# Trem-O-Drive.net
KiCad netlist of a schematic drawn in EAGLE
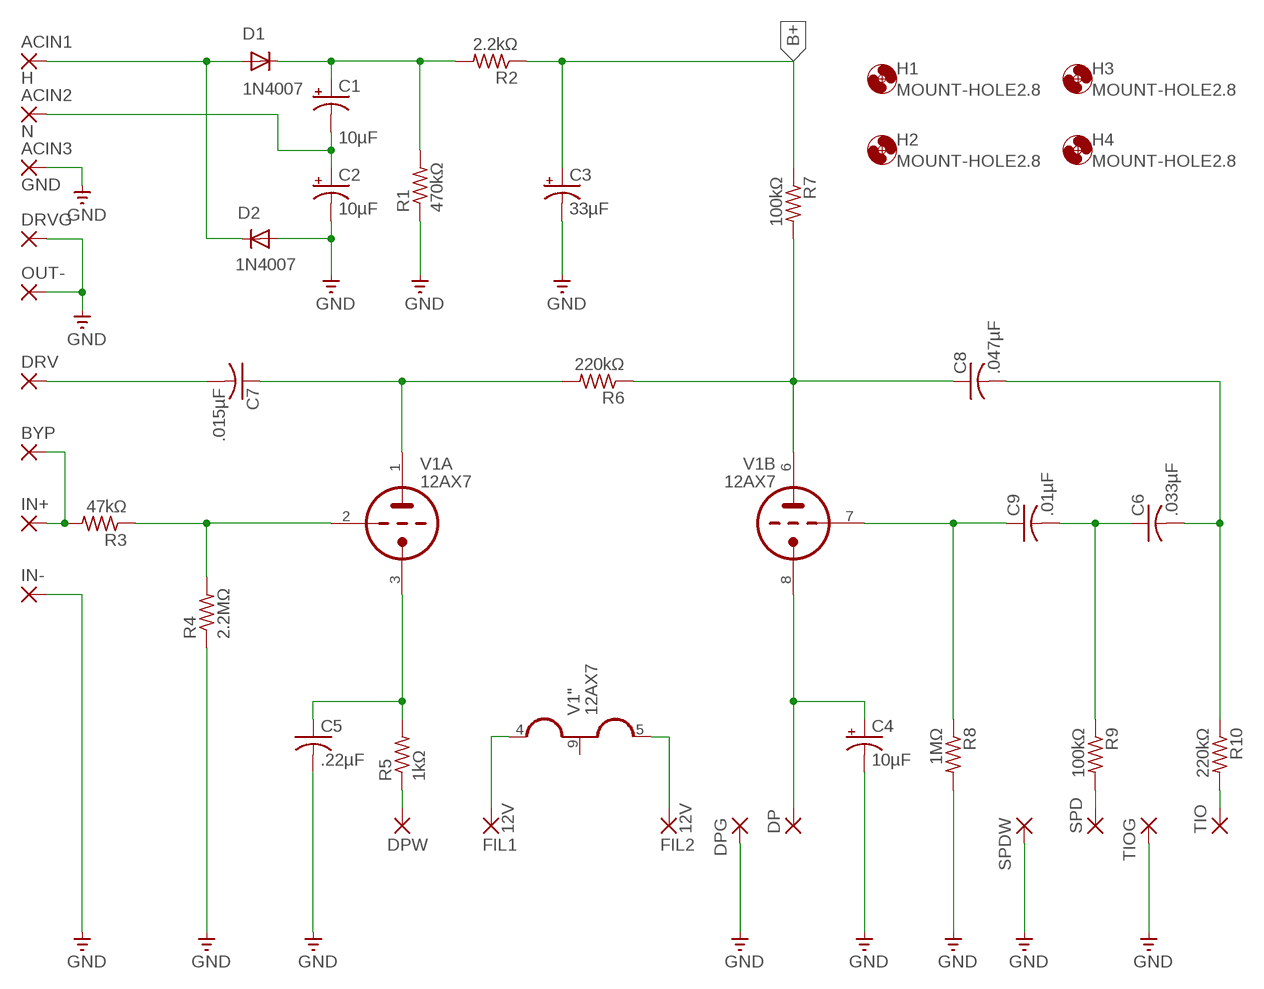
[diagram p0: schematic, sheet 1]

(export (version "E")
  (design (tool "Eeschema 10.0.6"))
  (components
    (comp (ref "ACIN1")
      (value "H")
      (footprint "eagle-import:3,81_1,4")
      (libsource (lib "eagle-import") (part "3,81/1,4"))
    )
    (comp (ref "ACIN2")
      (value "N")
      (footprint "eagle-import:3,81_1,4")
      (libsource (lib "eagle-import") (part "3,81/1,4"))
    )
    (comp (ref "ACIN3")
      (value "GND")
      (footprint "eagle-import:3,81_1,4")
      (libsource (lib "eagle-import") (part "3,81/1,4"))
    )
    (comp (ref "BYP")
      (value "3,81/1,4")
      (footprint "eagle-import:3,81_1,4")
      (libsource (lib "eagle-import") (part "3,81/1,4"))
    )
    (comp (ref "C1")
      (value "10µF")
      (footprint "eagle-import:E5-10,5")
      (libsource (lib "eagle-import") (part "CPOL-USE5-10.5"))
    )
    (comp (ref "C2")
      (value "10µF")
      (footprint "eagle-import:E5-10,5")
      (libsource (lib "eagle-import") (part "CPOL-USE5-10.5"))
    )
    (comp (ref "C3")
      (value "33µF")
      (footprint "eagle-import:E5-10,5")
      (libsource (lib "eagle-import") (part "CPOL-USE5-10.5"))
    )
    (comp (ref "C4")
      (value "10µF")
      (footprint "eagle-import:E5-10,5")
      (libsource (lib "eagle-import") (part "CPOL-USE5-10.5"))
    )
    (comp (ref "C5")
      (value ".22µF")
      (footprint "eagle-import:C150-064X183")
      (libsource (lib "eagle-import") (part "C-US150-064X183"))
    )
    (comp (ref "C6")
      (value ".033µF")
      (footprint "eagle-import:C102-064X133")
      (libsource (lib "eagle-import") (part "C-US102-064X133"))
    )
    (comp (ref "C7")
      (value ".015µF")
      (footprint "eagle-import:C102-064X133")
      (libsource (lib "eagle-import") (part "C-US102-064X133"))
    )
    (comp (ref "C8")
      (value ".047µF")
      (footprint "eagle-import:C102-064X133")
      (libsource (lib "eagle-import") (part "C-US102-064X133"))
    )
    (comp (ref "C9")
      (value ".01µF")
      (footprint "eagle-import:C102-064X133")
      (libsource (lib "eagle-import") (part "C-US102-064X133"))
    )
    (comp (ref "D1")
      (value "1N4007")
      (footprint "eagle-import:DIODE-1N4148")
      (libsource (lib "eagle-import") (part "DIODE1N4148"))
    )
    (comp (ref "D2")
      (value "1N4007")
      (footprint "eagle-import:DIODE-1N4148")
      (libsource (lib "eagle-import") (part "DIODE1N4148"))
    )
    (comp (ref "DP")
      (value "3,81/1,4")
      (footprint "eagle-import:3,81_1,4")
      (libsource (lib "eagle-import") (part "3,81/1,4"))
    )
    (comp (ref "DPG")
      (value "3,81/1,4")
      (footprint "eagle-import:3,81_1,4")
      (libsource (lib "eagle-import") (part "3,81/1,4"))
    )
    (comp (ref "DPW")
      (value "3,81/1,4")
      (footprint "eagle-import:3,81_1,4")
      (libsource (lib "eagle-import") (part "3,81/1,4"))
    )
    (comp (ref "DRV")
      (value "3,81/1,4")
      (footprint "eagle-import:3,81_1,4")
      (libsource (lib "eagle-import") (part "3,81/1,4"))
    )
    (comp (ref "DRVG")
      (value "3,81/1,4")
      (footprint "eagle-import:3,81_1,4")
      (libsource (lib "eagle-import") (part "3,81/1,4"))
    )
    (comp (ref "FIL1")
      (value "12V")
      (footprint "eagle-import:3,81_1,4")
      (libsource (lib "eagle-import") (part "3,81/1,4"))
    )
    (comp (ref "FIL2")
      (value "12V")
      (footprint "eagle-import:3,81_1,4")
      (libsource (lib "eagle-import") (part "3,81/1,4"))
    )
    (comp (ref "H1")
      (value "MOUNT-HOLE2.8")
      (footprint "eagle-import:2,8")
      (libsource (lib "eagle-import") (part "MOUNT-HOLE2.8"))
    )
    (comp (ref "H2")
      (value "MOUNT-HOLE2.8")
      (footprint "eagle-import:2,8")
      (libsource (lib "eagle-import") (part "MOUNT-HOLE2.8"))
    )
    (comp (ref "H3")
      (value "MOUNT-HOLE2.8")
      (footprint "eagle-import:2,8")
      (libsource (lib "eagle-import") (part "MOUNT-HOLE2.8"))
    )
    (comp (ref "H4")
      (value "MOUNT-HOLE2.8")
      (footprint "eagle-import:2,8")
      (libsource (lib "eagle-import") (part "MOUNT-HOLE2.8"))
    )
    (comp (ref "IN+")
      (value "3,81/1,4")
      (footprint "eagle-import:3,81_1,4")
      (libsource (lib "eagle-import") (part "3,81/1,4"))
    )
    (comp (ref "IN-")
      (value "3,81/1,4")
      (footprint "eagle-import:3,81_1,4")
      (libsource (lib "eagle-import") (part "3,81/1,4"))
    )
    (comp (ref "OUT-")
      (value "3,81/1,4")
      (footprint "eagle-import:3,81_1,4")
      (libsource (lib "eagle-import") (part "3,81/1,4"))
    )
    (comp (ref "R1")
      (value "470kΩ")
      (footprint "eagle-import:0411_12")
      (libsource (lib "eagle-import") (part "R-US_0411/12"))
    )
    (comp (ref "R2")
      (value "2.2kΩ")
      (footprint "eagle-import:0411_12")
      (libsource (lib "eagle-import") (part "R-US_0411/12"))
    )
    (comp (ref "R3")
      (value "47kΩ")
      (footprint "eagle-import:0411_12")
      (libsource (lib "eagle-import") (part "R-US_0411/12"))
    )
    (comp (ref "R4")
      (value "2.2MΩ")
      (footprint "eagle-import:0411_12")
      (libsource (lib "eagle-import") (part "R-US_0411/12"))
    )
    (comp (ref "R5")
      (value "1kΩ")
      (footprint "eagle-import:0411_12")
      (libsource (lib "eagle-import") (part "R-US_0411/12"))
    )
    (comp (ref "R6")
      (value "220kΩ")
      (footprint "eagle-import:0411_12")
      (libsource (lib "eagle-import") (part "R-US_0411/12"))
    )
    (comp (ref "R7")
      (value "100kΩ")
      (footprint "eagle-import:0411_12")
      (libsource (lib "eagle-import") (part "R-US_0411/12"))
    )
    (comp (ref "R8")
      (value "1MΩ")
      (footprint "eagle-import:0411_12")
      (libsource (lib "eagle-import") (part "R-US_0411/12"))
    )
    (comp (ref "R9")
      (value "100kΩ")
      (footprint "eagle-import:0411_12")
      (libsource (lib "eagle-import") (part "R-US_0411/12"))
    )
    (comp (ref "R10")
      (value "220kΩ")
      (footprint "eagle-import:0411_12")
      (libsource (lib "eagle-import") (part "R-US_0411/12"))
    )
    (comp (ref "SPD")
      (value "3,81/1,4")
      (footprint "eagle-import:3,81_1,4")
      (libsource (lib "eagle-import") (part "3,81/1,4"))
    )
    (comp (ref "SPDW")
      (value "3,81/1,4")
      (footprint "eagle-import:3,81_1,4")
      (libsource (lib "eagle-import") (part "3,81/1,4"))
    )
    (comp (ref "TIO")
      (value "3,81/1,4")
      (footprint "eagle-import:3,81_1,4")
      (libsource (lib "eagle-import") (part "3,81/1,4"))
    )
    (comp (ref "TIOG")
      (value "3,81/1,4")
      (footprint "eagle-import:3,81_1,4")
      (libsource (lib "eagle-import") (part "3,81/1,4"))
    )
    (comp (ref "V1")
      (value "12AX7")
      (footprint "eagle-import:NOVAL")
      (libsource (lib "eagle-import") (part "12AX7-P"))
    )
  )
  (nets
    (net (code "1") (name "B+") (class "Default")
      (node (ref "C3") (pin "+") (pinfunction "+_+") (pintype "passive"))
      (node (ref "R2") (pin "1") (pinfunction "1_1") (pintype "passive"))
      (node (ref "R7") (pin "1") (pinfunction "1_1") (pintype "passive"))
    )
    (net (code "2") (name "GND") (class "Default")
      (node (ref "ACIN3") (pin "1") (pinfunction "P_1") (pintype "passive"))
      (node (ref "C2") (pin "-") (pinfunction "-_-") (pintype "passive"))
      (node (ref "C3") (pin "-") (pinfunction "-_-") (pintype "passive"))
      (node (ref "C4") (pin "-") (pinfunction "-_-") (pintype "passive"))
      (node (ref "C5") (pin "2") (pinfunction "2_2") (pintype "passive"))
      (node (ref "D2") (pin "A") (pinfunction "A_A") (pintype "passive"))
      (node (ref "DPG") (pin "1") (pinfunction "P_1") (pintype "passive"))
      (node (ref "DRVG") (pin "1") (pinfunction "P_1") (pintype "passive"))
      (node (ref "IN-") (pin "1") (pinfunction "P_1") (pintype "passive"))
      (node (ref "OUT-") (pin "1") (pinfunction "P_1") (pintype "passive"))
      (node (ref "R1") (pin "1") (pinfunction "1_1") (pintype "passive"))
      (node (ref "R4") (pin "1") (pinfunction "1_1") (pintype "passive"))
      (node (ref "R8") (pin "2") (pinfunction "2_2") (pintype "passive"))
      (node (ref "SPDW") (pin "1") (pinfunction "P_1") (pintype "passive"))
      (node (ref "TIOG") (pin "1") (pinfunction "P_1") (pintype "passive"))
    )
    (net (code "3") (name "Net-(ACIN1-P)") (class "Default")
      (node (ref "ACIN1") (pin "1") (pinfunction "P_1") (pintype "passive"))
      (node (ref "D1") (pin "A") (pinfunction "A_A") (pintype "passive"))
      (node (ref "D2") (pin "C") (pinfunction "C_C") (pintype "passive"))
    )
    (net (code "4") (name "Net-(ACIN2-P)") (class "Default")
      (node (ref "ACIN2") (pin "1") (pinfunction "P_1") (pintype "passive"))
      (node (ref "C1") (pin "-") (pinfunction "-_-") (pintype "passive"))
      (node (ref "C2") (pin "+") (pinfunction "+_+") (pintype "passive"))
    )
    (net (code "5") (name "Net-(BYP-P)") (class "Default")
      (node (ref "BYP") (pin "1") (pinfunction "P_1") (pintype "passive"))
      (node (ref "IN+") (pin "1") (pinfunction "P_1") (pintype "passive"))
      (node (ref "R3") (pin "2") (pinfunction "2_2") (pintype "passive"))
    )
    (net (code "6") (name "Net-(C1-Pad+)") (class "Default")
      (node (ref "C1") (pin "+") (pinfunction "+_+") (pintype "passive"))
      (node (ref "D1") (pin "C") (pinfunction "C_C") (pintype "passive"))
      (node (ref "R1") (pin "2") (pinfunction "2_2") (pintype "passive"))
      (node (ref "R2") (pin "2") (pinfunction "2_2") (pintype "passive"))
    )
    (net (code "7") (name "Net-(C6-Pad1)") (class "Default")
      (node (ref "C6") (pin "1") (pinfunction "1_1") (pintype "passive"))
      (node (ref "C9") (pin "2") (pinfunction "2_2") (pintype "passive"))
      (node (ref "R9") (pin "1") (pinfunction "1_1") (pintype "passive"))
    )
    (net (code "8") (name "Net-(C6-Pad2)") (class "Default")
      (node (ref "C6") (pin "2") (pinfunction "2_2") (pintype "passive"))
      (node (ref "C8") (pin "2") (pinfunction "2_2") (pintype "passive"))
      (node (ref "R10") (pin "1") (pinfunction "1_1") (pintype "passive"))
    )
    (net (code "9") (name "Net-(DP-P)") (class "Default")
      (node (ref "C4") (pin "+") (pinfunction "+_+") (pintype "passive"))
      (node (ref "DP") (pin "1") (pinfunction "P_1") (pintype "passive"))
      (node (ref "V1") (pin "8") (pinfunction "TK_8") (pintype "passive"))
    )
    (net (code "10") (name "Net-(DPW-P)") (class "Default")
      (node (ref "DPW") (pin "1") (pinfunction "P_1") (pintype "passive"))
      (node (ref "R5") (pin "1") (pinfunction "1_1") (pintype "passive"))
    )
    (net (code "11") (name "Net-(DRV-P)") (class "Default")
      (node (ref "C7") (pin "2") (pinfunction "2_2") (pintype "passive"))
      (node (ref "DRV") (pin "1") (pinfunction "P_1") (pintype "passive"))
    )
    (net (code "12") (name "Net-(FIL1-P)") (class "Default")
      (node (ref "FIL1") (pin "1") (pinfunction "P_1") (pintype "passive"))
      (node (ref "V1") (pin "4") (pinfunction "H1_4") (pintype "passive"))
    )
    (net (code "13") (name "Net-(FIL2-P)") (class "Default")
      (node (ref "FIL2") (pin "1") (pinfunction "P_1") (pintype "passive"))
      (node (ref "V1") (pin "5") (pinfunction "H3_5") (pintype "passive"))
    )
    (net (code "14") (name "Net-(SPD-P)") (class "Default")
      (node (ref "R9") (pin "2") (pinfunction "2_2") (pintype "passive"))
      (node (ref "SPD") (pin "1") (pinfunction "P_1") (pintype "passive"))
    )
    (net (code "15") (name "Net-(TIO-P)") (class "Default")
      (node (ref "R10") (pin "2") (pinfunction "2_2") (pintype "passive"))
      (node (ref "TIO") (pin "1") (pinfunction "P_1") (pintype "passive"))
    )
    (net (code "16") (name "Net-(V1B-TA)") (class "Default")
      (node (ref "C7") (pin "1") (pinfunction "1_1") (pintype "passive"))
      (node (ref "R6") (pin "2") (pinfunction "2_2") (pintype "passive"))
      (node (ref "V1") (pin "1") (pinfunction "TA_1") (pintype "passive"))
    )
    (net (code "17") (name "Net-(V1B-TG)") (class "Default")
      (node (ref "R3") (pin "1") (pinfunction "1_1") (pintype "passive"))
      (node (ref "R4") (pin "2") (pinfunction "2_2") (pintype "passive"))
      (node (ref "V1") (pin "2") (pinfunction "TG_2") (pintype "passive"))
    )
    (net (code "18") (name "Net-(V1B-TK)") (class "Default")
      (node (ref "C5") (pin "1") (pinfunction "1_1") (pintype "passive"))
      (node (ref "R5") (pin "2") (pinfunction "2_2") (pintype "passive"))
      (node (ref "V1") (pin "3") (pinfunction "TK_3") (pintype "passive"))
    )
    (net (code "19") (name "Net-(V1C-TA)") (class "Default")
      (node (ref "C8") (pin "1") (pinfunction "1_1") (pintype "passive"))
      (node (ref "R6") (pin "1") (pinfunction "1_1") (pintype "passive"))
      (node (ref "R7") (pin "2") (pinfunction "2_2") (pintype "passive"))
      (node (ref "V1") (pin "6") (pinfunction "TA_6") (pintype "passive"))
    )
    (net (code "20") (name "Net-(V1C-TG)") (class "Default")
      (node (ref "C9") (pin "1") (pinfunction "1_1") (pintype "passive"))
      (node (ref "R8") (pin "1") (pinfunction "1_1") (pintype "passive"))
      (node (ref "V1") (pin "7") (pinfunction "TG_7") (pintype "passive"))
    )
    (net (code "21") (name "unconnected-(V1A-H2-Pad9)") (class "Default")
      (node (ref "V1") (pin "9") (pinfunction "H2_9") (pintype "passive"))
    )
  )
)
